# RightInterface.net
KiCad netlist of a schematic drawn in Altium Designer
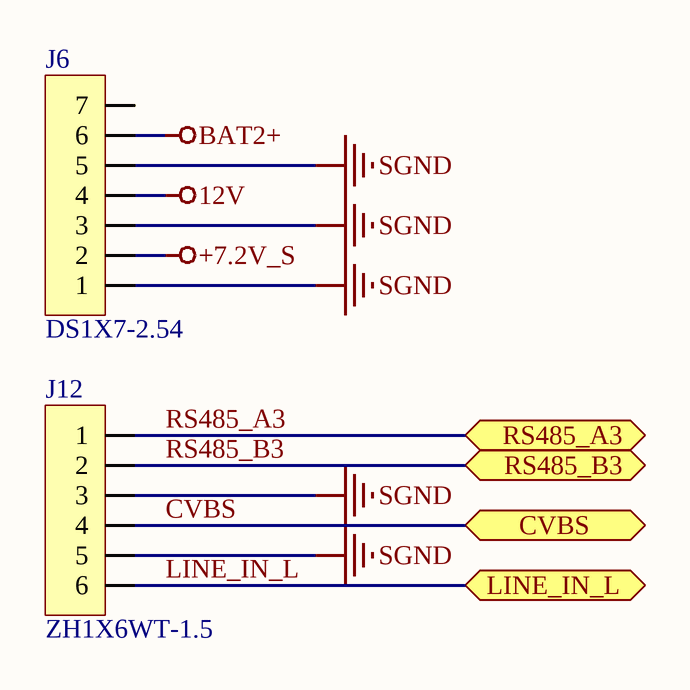
[diagram p0: RightInterface.SchDoc]

(export (version "E")
  (design (tool "Eeschema 10.0.6"))
  (components
    (comp (ref "J6")
      (value "DS1X7-2.54")
      (footprint "DS1X7H-2.54")
      (libsource (lib "Connector Class") (part "HEADER1X7"))
    )
    (comp (ref "J12")
      (value "ZH1X6WT-1.5")
      (footprint "ZH1X6WT-1.5")
      (libsource (lib "Connector Class") (part "HEADER1X6"))
    )
  )
  (nets
    (net (code "1") (name "+7.2V_S") (class "Default")
      (node (ref "J6") (pin "2") (pinfunction "2_2") (pintype "passive"))
    )
    (net (code "2") (name "/CVBS") (class "Default")
      (node (ref "J12") (pin "4") (pinfunction "4_4") (pintype "passive"))
    )
    (net (code "3") (name "/LINE_IN_L") (class "Default")
      (node (ref "J12") (pin "6") (pinfunction "6_6") (pintype "passive"))
    )
    (net (code "4") (name "/RS485_A3") (class "Default")
      (node (ref "J12") (pin "1") (pinfunction "1_1") (pintype "passive"))
    )
    (net (code "5") (name "/RS485_B3") (class "Default")
      (node (ref "J12") (pin "2") (pinfunction "2_2") (pintype "passive"))
    )
    (net (code "6") (name "12V") (class "Default")
      (node (ref "J6") (pin "4") (pinfunction "4_4") (pintype "passive"))
    )
    (net (code "7") (name "BAT2+") (class "Default")
      (node (ref "J6") (pin "6") (pinfunction "6_6") (pintype "passive"))
    )
    (net (code "8") (name "SGND") (class "Default")
      (node (ref "J12") (pin "3") (pinfunction "3_3") (pintype "passive"))
      (node (ref "J12") (pin "5") (pinfunction "5_5") (pintype "passive"))
      (node (ref "J6") (pin "1") (pinfunction "1_1") (pintype "passive"))
      (node (ref "J6") (pin "3") (pinfunction "3_3") (pintype "passive"))
      (node (ref "J6") (pin "5") (pinfunction "5_5") (pintype "passive"))
    )
    (net (code "9") (name "unconnected-(J6-Pad7)") (class "Default")
      (node (ref "J6") (pin "7") (pinfunction "7_7") (pintype "passive"))
    )
  )
)
